# controladorCarga.net
KiCad netlist of a schematic drawn in EAGLE
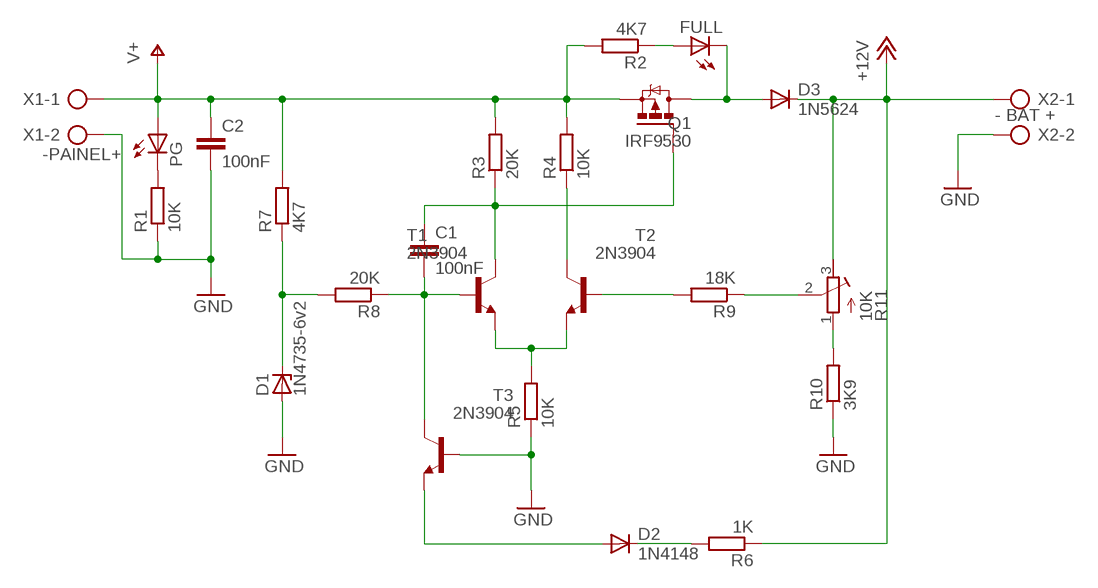
[diagram p0: schematic, sheet 1]

(export (version "E")
  (design (tool "Eeschema 10.0.6"))
  (components
    (comp (ref "C1")
      (value "100nF")
      (footprint "eagle-import:C050-025X075")
      (libsource (lib "eagle-import") (part "C-EU050-025X075"))
    )
    (comp (ref "C2")
      (value "100nF")
      (footprint "eagle-import:C050-025X075")
      (libsource (lib "eagle-import") (part "C-EU050-025X075"))
    )
    (comp (ref "D1")
      (value "1N4735-6v2")
      (footprint "eagle-import:DO41Z10")
      (libsource (lib "eagle-import") (part "1N4728"))
    )
    (comp (ref "D2")
      (value "1N4148")
      (footprint "eagle-import:DO35-7")
      (libsource (lib "eagle-import") (part "1N4148DO35-7"))
    )
    (comp (ref "D3")
      (value "1N5624")
      (footprint "eagle-import:DO201-15")
      (libsource (lib "eagle-import") (part "1N5624"))
    )
    (comp (ref "FULL")
      (value "LED5MM")
      (footprint "eagle-import:LED5MM")
      (libsource (lib "eagle-import") (part "LED5MM"))
    )
    (comp (ref "PG")
      (value "LED5MM")
      (footprint "eagle-import:LED5MM")
      (libsource (lib "eagle-import") (part "LED5MM"))
    )
    (comp (ref "Q1")
      (value "IRF9530")
      (footprint "eagle-import:TO220BV")
      (libsource (lib "eagle-import") (part "IRF9530"))
    )
    (comp (ref "R1")
      (value "10K")
      (footprint "eagle-import:0207_10")
      (libsource (lib "eagle-import") (part "R-EU_0207/10"))
    )
    (comp (ref "R2")
      (value "4K7")
      (footprint "eagle-import:0207_10")
      (libsource (lib "eagle-import") (part "R-EU_0207/10"))
    )
    (comp (ref "R3")
      (value "20K")
      (footprint "eagle-import:0207_10")
      (libsource (lib "eagle-import") (part "R-EU_0207/10"))
    )
    (comp (ref "R4")
      (value "10K")
      (footprint "eagle-import:0207_10")
      (libsource (lib "eagle-import") (part "R-EU_0207/10"))
    )
    (comp (ref "R5")
      (value "10K")
      (footprint "eagle-import:0207_10")
      (libsource (lib "eagle-import") (part "R-EU_0207/10"))
    )
    (comp (ref "R6")
      (value "1K")
      (footprint "eagle-import:0207_10")
      (libsource (lib "eagle-import") (part "R-EU_0207/10"))
    )
    (comp (ref "R7")
      (value "4K7")
      (footprint "eagle-import:0207_10")
      (libsource (lib "eagle-import") (part "R-EU_0207/10"))
    )
    (comp (ref "R8")
      (value "20K")
      (footprint "eagle-import:0204_7")
      (libsource (lib "eagle-import") (part "R-EU_0204/7"))
    )
    (comp (ref "R9")
      (value "18K")
      (footprint "eagle-import:0207_10")
      (libsource (lib "eagle-import") (part "R-EU_0207/10"))
    )
    (comp (ref "R10")
      (value "3K9")
      (footprint "eagle-import:0204_7")
      (libsource (lib "eagle-import") (part "R-EU_0204/7"))
    )
    (comp (ref "R11")
      (value "10K")
      (footprint "eagle-import:RTRIM3339P")
      (libsource (lib "eagle-import") (part "R-TRIMM3339P"))
    )
    (comp (ref "T1")
      (value "2N3904")
      (footprint "eagle-import:TO92")
      (libsource (lib "eagle-import") (part "2N3904"))
    )
    (comp (ref "T2")
      (value "2N3904")
      (footprint "eagle-import:TO92")
      (libsource (lib "eagle-import") (part "2N3904"))
    )
    (comp (ref "T3")
      (value "2N3904")
      (footprint "eagle-import:TO92")
      (libsource (lib "eagle-import") (part "2N3904"))
    )
    (comp (ref "X1")
      (value "-PAINEL+")
      (footprint "eagle-import:AK500_2")
      (libsource (lib "eagle-import") (part "AK500/2"))
    )
    (comp (ref "X2")
      (value "- BAT +")
      (footprint "eagle-import:AK500_2")
      (libsource (lib "eagle-import") (part "AK500/2"))
    )
  )
  (nets
    (net (code "1") (name "+12V") (class "Default")
      (node (ref "D3") (pin "C") (pinfunction "C_C") (pintype "passive"))
      (node (ref "R11") (pin "3") (pinfunction "E_3") (pintype "passive"))
      (node (ref "R6") (pin "1") (pinfunction "1_1") (pintype "passive"))
      (node (ref "X2") (pin "1") (pinfunction "KL_1") (pintype "passive"))
    )
    (net (code "2") (name "GND") (class "Default")
      (node (ref "C2") (pin "2") (pinfunction "2_2") (pintype "passive"))
      (node (ref "D1") (pin "A") (pinfunction "A_A") (pintype "passive"))
      (node (ref "R1") (pin "1") (pinfunction "1_1") (pintype "passive"))
      (node (ref "R10") (pin "1") (pinfunction "1_1") (pintype "passive"))
      (node (ref "R5") (pin "1") (pinfunction "1_1") (pintype "passive"))
      (node (ref "T3") (pin "2") (pinfunction "B_2") (pintype "passive"))
      (node (ref "X1") (pin "2") (pinfunction "KL_2") (pintype "passive"))
      (node (ref "X2") (pin "2") (pinfunction "KL_2") (pintype "passive"))
    )
    (net (code "3") (name "Net-(D1-PadC)") (class "Default")
      (node (ref "D1") (pin "C") (pinfunction "C_C") (pintype "passive"))
      (node (ref "R7") (pin "1") (pinfunction "1_1") (pintype "passive"))
      (node (ref "R8") (pin "2") (pinfunction "2_2") (pintype "passive"))
    )
    (net (code "4") (name "Net-(D2-PadC)") (class "Default")
      (node (ref "D2") (pin "C") (pinfunction "C_C") (pintype "passive"))
      (node (ref "R6") (pin "2") (pinfunction "2_2") (pintype "passive"))
    )
    (net (code "5") (name "Net-(FULL-C)") (class "Default")
      (node (ref "D3") (pin "A") (pinfunction "A_A") (pintype "passive"))
      (node (ref "FULL") (pin "K") (pinfunction "C_K") (pintype "passive"))
      (node (ref "Q1") (pin "D") (pinfunction "D_D") (pintype "passive"))
    )
    (net (code "6") (name "Net-(FULL-PadA)") (class "Default")
      (node (ref "FULL") (pin "A") (pinfunction "A_A") (pintype "passive"))
      (node (ref "R2") (pin "1") (pinfunction "1_1") (pintype "passive"))
    )
    (net (code "7") (name "Net-(PG-C)") (class "Default")
      (node (ref "PG") (pin "K") (pinfunction "C_K") (pintype "passive"))
      (node (ref "R1") (pin "2") (pinfunction "2_2") (pintype "passive"))
    )
    (net (code "8") (name "Net-(R11-A)") (class "Default")
      (node (ref "R10") (pin "2") (pinfunction "2_2") (pintype "passive"))
      (node (ref "R11") (pin "1") (pinfunction "A_1") (pintype "passive"))
    )
    (net (code "9") (name "Net-(R11-S)") (class "Default")
      (node (ref "R11") (pin "2") (pinfunction "S_2") (pintype "passive"))
      (node (ref "R9") (pin "1") (pinfunction "1_1") (pintype "passive"))
    )
    (net (code "10") (name "Net-(T1-B)") (class "Default")
      (node (ref "C1") (pin "2") (pinfunction "2_2") (pintype "passive"))
      (node (ref "R8") (pin "1") (pinfunction "1_1") (pintype "passive"))
      (node (ref "T1") (pin "2") (pinfunction "B_2") (pintype "passive"))
      (node (ref "T3") (pin "1") (pinfunction "C_1") (pintype "passive"))
    )
    (net (code "11") (name "Net-(T1-C)") (class "Default")
      (node (ref "C1") (pin "1") (pinfunction "1_1") (pintype "passive"))
      (node (ref "Q1") (pin "G") (pinfunction "G_G") (pintype "passive"))
      (node (ref "R3") (pin "1") (pinfunction "1_1") (pintype "passive"))
      (node (ref "T1") (pin "1") (pinfunction "C_1") (pintype "passive"))
    )
    (net (code "12") (name "Net-(T1-E)") (class "Default")
      (node (ref "R5") (pin "2") (pinfunction "2_2") (pintype "passive"))
      (node (ref "T1") (pin "3") (pinfunction "E_3") (pintype "passive"))
      (node (ref "T2") (pin "3") (pinfunction "E_3") (pintype "passive"))
    )
    (net (code "13") (name "Net-(T2-B)") (class "Default")
      (node (ref "R9") (pin "2") (pinfunction "2_2") (pintype "passive"))
      (node (ref "T2") (pin "2") (pinfunction "B_2") (pintype "passive"))
    )
    (net (code "14") (name "Net-(T2-C)") (class "Default")
      (node (ref "R4") (pin "1") (pinfunction "1_1") (pintype "passive"))
      (node (ref "T2") (pin "1") (pinfunction "C_1") (pintype "passive"))
    )
    (net (code "15") (name "Net-(T3-E)") (class "Default")
      (node (ref "D2") (pin "A") (pinfunction "A_A") (pintype "passive"))
      (node (ref "T3") (pin "3") (pinfunction "E_3") (pintype "passive"))
    )
    (net (code "16") (name "V+") (class "Default")
      (node (ref "C2") (pin "1") (pinfunction "1_1") (pintype "passive"))
      (node (ref "PG") (pin "A") (pinfunction "A_A") (pintype "passive"))
      (node (ref "Q1") (pin "S") (pinfunction "S_S") (pintype "passive"))
      (node (ref "R2") (pin "2") (pinfunction "2_2") (pintype "passive"))
      (node (ref "R3") (pin "2") (pinfunction "2_2") (pintype "passive"))
      (node (ref "R4") (pin "2") (pinfunction "2_2") (pintype "passive"))
      (node (ref "R7") (pin "2") (pinfunction "2_2") (pintype "passive"))
      (node (ref "X1") (pin "1") (pinfunction "KL_1") (pintype "passive"))
    )
  )
)
